# CATS-EUROC-IMU.net
KiCad netlist of a schematic drawn in Altium Designer
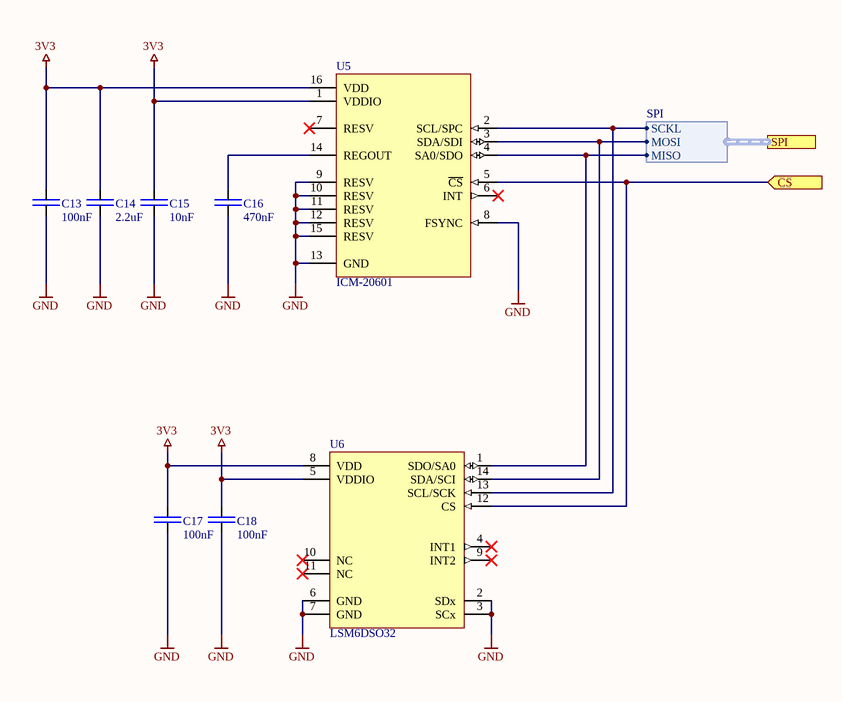
[diagram p0: CATS-EUROC-IMU.SchDoc]

(export (version "E")
  (design (tool "Eeschema 10.0.6"))
  (components
    (comp (ref "C13")
      (value "100nF")
      (footprint "SMD Keramikkondensator 0402")
      (description "SMD Ceramic Capacitor E6")
      (libsource (lib "CATS-EUROC") (part "E6 - 100nF"))
    )
    (comp (ref "C14")
      (value "2.2uF")
      (footprint "SMD Keramikkondensator 0402")
      (description "SMD Ceramic Capacitor E6")
      (libsource (lib "CATS-EUROC") (part "E6 - 2.2uF"))
    )
    (comp (ref "C15")
      (value "10nF")
      (footprint "SMD Keramikkondensator 0402")
      (description "SMD Ceramic Capacitor E6")
      (libsource (lib "CATS-EUROC") (part "E6 - 10nF"))
    )
    (comp (ref "C16")
      (value "470nF")
      (footprint "SMD Keramikkondensator 0402")
      (description "SMD Ceramic Capacitor E6")
      (libsource (lib "CATS-EUROC") (part "E6 - 470nF"))
    )
    (comp (ref "C17")
      (value "100nF")
      (footprint "SMD Keramikkondensator 0402")
      (description "SMD Ceramic Capacitor E6")
      (libsource (lib "CATS-EUROC") (part "E6 - 100nF"))
    )
    (comp (ref "C18")
      (value "100nF")
      (footprint "SMD Keramikkondensator 0402")
      (description "SMD Ceramic Capacitor E6")
      (libsource (lib "CATS-EUROC") (part "E6 - 100nF"))
    )
    (comp (ref "U5")
      (value "ICM-20601")
      (footprint "SMD IC LGA-16 5/3")
      (description "World’s First Wide-Range 6-Axis MotionTracking Device for High Speed Applications")
      (libsource (lib "Sensors") (part "ICM-20601"))
    )
    (comp (ref "U6")
      (value "LSM6DSO32")
      (footprint "SMD IC LGA-14")
      (description "iNEMO inertial module\r\n±4/±8/±16/±32 g \r\n±125/±250/±500/±1000/±2000 dps")
      (libsource (lib "Sensors") (part "LSM6DSO32"))
    )
  )
  (nets
    (net (code "2") (name "/CS") (class "Default")
      (node (ref "U5") (pin "5") (pinfunction "~{CS}_5") (pintype "input"))
      (node (ref "U6") (pin "12") (pinfunction "CS_12") (pintype "input"))
    )
    (net (code "4") (name "3V3") (class "Default")
      (node (ref "C13") (pin "2") (pinfunction "2_2") (pintype "passive"))
      (node (ref "C14") (pin "2") (pinfunction "2_2") (pintype "passive"))
      (node (ref "C15") (pin "2") (pinfunction "2_2") (pintype "passive"))
      (node (ref "C17") (pin "2") (pinfunction "2_2") (pintype "passive"))
      (node (ref "C18") (pin "2") (pinfunction "2_2") (pintype "passive"))
      (node (ref "U5") (pin "1") (pinfunction "VDDIO_1") (pintype "power_in"))
      (node (ref "U5") (pin "16") (pinfunction "VDD_16") (pintype "power_in"))
      (node (ref "U6") (pin "5") (pinfunction "VDDIO_5") (pintype "passive"))
      (node (ref "U6") (pin "8") (pinfunction "VDD_8") (pintype "passive"))
    )
    (net (code "5") (name "GND") (class "Default")
      (node (ref "C13") (pin "1") (pinfunction "1_1") (pintype "passive"))
      (node (ref "C14") (pin "1") (pinfunction "1_1") (pintype "passive"))
      (node (ref "C15") (pin "1") (pinfunction "1_1") (pintype "passive"))
      (node (ref "C16") (pin "1") (pinfunction "1_1") (pintype "passive"))
      (node (ref "C17") (pin "1") (pinfunction "1_1") (pintype "passive"))
      (node (ref "C18") (pin "1") (pinfunction "1_1") (pintype "passive"))
      (node (ref "U5") (pin "10") (pinfunction "RESV_10") (pintype "passive"))
      (node (ref "U5") (pin "11") (pinfunction "RESV_11") (pintype "passive"))
      (node (ref "U5") (pin "12") (pinfunction "RESV_12") (pintype "passive"))
      (node (ref "U5") (pin "13") (pinfunction "GND_13") (pintype "power_in"))
      (node (ref "U5") (pin "15") (pinfunction "RESV_15") (pintype "passive"))
      (node (ref "U5") (pin "8") (pinfunction "FSYNC_8") (pintype "input"))
      (node (ref "U5") (pin "9") (pinfunction "RESV_9") (pintype "passive"))
      (node (ref "U6") (pin "2") (pinfunction "SDx_2") (pintype "passive"))
      (node (ref "U6") (pin "3") (pinfunction "SCx_3") (pintype "passive"))
      (node (ref "U6") (pin "6") (pinfunction "GND_6") (pintype "passive"))
      (node (ref "U6") (pin "7") (pinfunction "GND_7") (pintype "passive"))
    )
    (net (code "6") (name "Net-(U5-REGOUT)") (class "Default")
      (node (ref "C16") (pin "2") (pinfunction "2_2") (pintype "passive"))
      (node (ref "U5") (pin "14") (pinfunction "REGOUT_14") (pintype "power_in"))
    )
    (net (code "7") (name "Net-(U5-SA0{slash}SDO)") (class "Default")
      (node (ref "U5") (pin "4") (pinfunction "SA0/SDO_4") (pintype "bidirectional"))
      (node (ref "U6") (pin "1") (pinfunction "SDO/SA0_1") (pintype "bidirectional"))
    )
    (net (code "8") (name "Net-(U5-SCL{slash}SPC)") (class "Default")
      (node (ref "U5") (pin "2") (pinfunction "SCL/SPC_2") (pintype "input"))
      (node (ref "U6") (pin "13") (pinfunction "SCL/SCK_13") (pintype "input"))
    )
    (net (code "9") (name "Net-(U5-SDA{slash}SDI)") (class "Default")
      (node (ref "U5") (pin "3") (pinfunction "SDA/SDI_3") (pintype "bidirectional"))
      (node (ref "U6") (pin "14") (pinfunction "SDA/SCI_14") (pintype "bidirectional"))
    )
    (net (code "10") (name "unconnected-(U5-INT-Pad6)") (class "Default")
      (node (ref "U5") (pin "6") (pinfunction "INT_6") (pintype "output+no_connect"))
    )
    (net (code "11") (name "unconnected-(U5-RESV-Pad7)") (class "Default")
      (node (ref "U5") (pin "7") (pinfunction "RESV_7") (pintype "passive+no_connect"))
    )
    (net (code "12") (name "unconnected-(U6-INT1-Pad4)") (class "Default")
      (node (ref "U6") (pin "4") (pinfunction "INT1_4") (pintype "output+no_connect"))
    )
    (net (code "13") (name "unconnected-(U6-INT2-Pad9)") (class "Default")
      (node (ref "U6") (pin "9") (pinfunction "INT2_9") (pintype "output+no_connect"))
    )
    (net (code "14") (name "unconnected-(U6-NC-Pad10)") (class "Default")
      (node (ref "U6") (pin "10") (pinfunction "NC_10") (pintype "passive+no_connect"))
    )
    (net (code "15") (name "unconnected-(U6-NC-Pad11)") (class "Default")
      (node (ref "U6") (pin "11") (pinfunction "NC_11") (pintype "passive+no_connect"))
    )
  )
)
